# 7_Inch_Module.net
KiCad netlist of a schematic drawn in Altium Designer
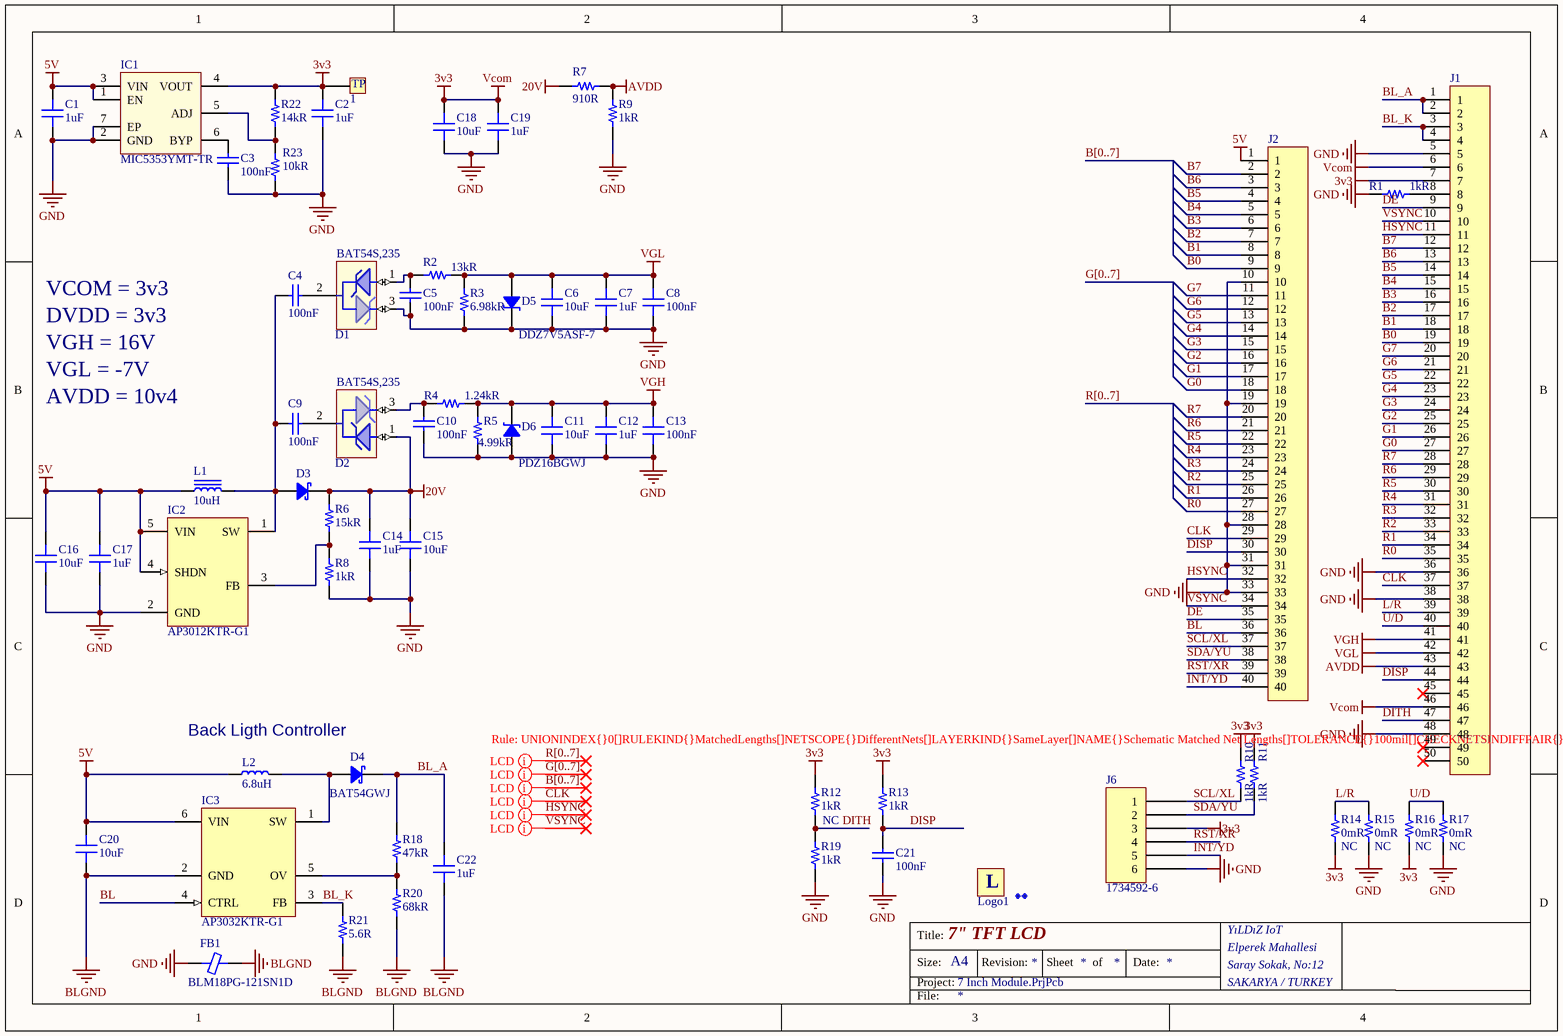
[diagram p0: 7 Inch Module.SchDoc]

(export (version "E")
  (design (tool "Eeschema 10.0.6"))
  (components
    (comp (ref "1")
      (value "Test Point")
      (footprint "TestPoint")
      (description "Custom Test Point")
      (libsource (lib "Muhammet_All_In_One") (part "Test Point"))
    )
    (comp (ref "C1")
      (value "1uF")
      (footprint "CAP 0603/1608")
      (description "Ceramic, SMT Capacitor")
      (fields
        (field (name "MANUFACTURER") "Samsung")
        (field (name "MANUFACTURER PART NUMBER") "CL10A105KP8NNNC")
      )
      (libsource (lib "yildizIoT Library") (part "Capacitor - Ceramic"))
    )
    (comp (ref "C2")
      (value "1uF")
      (footprint "CAP 0603/1608")
      (description "Ceramic, SMT Capacitor")
      (fields
        (field (name "MANUFACTURER") "Samsung")
        (field (name "MANUFACTURER PART NUMBER") "CL10A105KP8NNNC")
      )
      (libsource (lib "yildizIoT Library") (part "Capacitor - Ceramic"))
    )
    (comp (ref "C3")
      (value "100nF")
      (footprint "CAP 0603/1608")
      (description "Capacitor, Ceramic")
      (fields
        (field (name "MANUFACTURER") "Samsung")
        (field (name "MANUFACTURER PART NUMBER") "CL10A104KA8NNNC")
      )
      (libsource (lib "Muhammet_All_In_One") (part "Cap - Ceramic"))
    )
    (comp (ref "C4")
      (value "100nF")
      (footprint "CAP 0603/1608")
      (description "Capacitor, Ceramic")
      (fields
        (field (name "MANUFACTURER") "Samsung")
        (field (name "MANUFACTURER PART NUMBER") "CL10A104KA8NNNC")
      )
      (libsource (lib "Muhammet_All_In_One") (part "Cap - Ceramic"))
    )
    (comp (ref "C5")
      (value "100nF")
      (footprint "CAP 0603/1608")
      (description "Capacitor, Ceramic")
      (fields
        (field (name "MANUFACTURER") "Samsung")
        (field (name "MANUFACTURER PART NUMBER") "CL10A104KA8NNNC")
      )
      (libsource (lib "Muhammet_All_In_One") (part "Cap - Ceramic"))
    )
    (comp (ref "C6")
      (value "10uF")
      (footprint "CAP 0603/1608")
      (description "Ceramic, SMT Capacitor")
      (fields
        (field (name "MANUFACTURER") "Samsung")
        (field (name "MANUFACTURER PART NUMBER") "CL10A106MQ8NNNC")
      )
      (libsource (lib "yildizIoT Library") (part "Capacitor - Ceramic"))
    )
    (comp (ref "C7")
      (value "1uF")
      (footprint "CAP 0603/1608")
      (description "Ceramic, SMT Capacitor")
      (fields
        (field (name "MANUFACTURER") "Samsung")
        (field (name "MANUFACTURER PART NUMBER") "CL10A105KP8NNNC")
      )
      (libsource (lib "yildizIoT Library") (part "Capacitor - Ceramic"))
    )
    (comp (ref "C8")
      (value "100nF")
      (footprint "CAP 0603/1608")
      (description "Ceramic, SMT Capacitor")
      (fields
        (field (name "MANUFACTURER") "Samsung")
        (field (name "MANUFACTURER PART NUMBER") "CL10A104KA8NNNC")
      )
      (libsource (lib "yildizIoT Library") (part "Capacitor - Ceramic"))
    )
    (comp (ref "C9")
      (value "100nF")
      (footprint "CAP 0603/1608")
      (description "Capacitor, Ceramic")
      (fields
        (field (name "MANUFACTURER") "Samsung")
        (field (name "MANUFACTURER PART NUMBER") "CL10A104KA8NNNC")
      )
      (libsource (lib "Muhammet_All_In_One") (part "Cap - Ceramic"))
    )
    (comp (ref "C10")
      (value "100nF")
      (footprint "CAP 0603/1608")
      (description "Capacitor, Ceramic")
      (fields
        (field (name "MANUFACTURER") "Samsung")
        (field (name "MANUFACTURER PART NUMBER") "CL10A104KA8NNNC")
      )
      (libsource (lib "Muhammet_All_In_One") (part "Cap - Ceramic"))
    )
    (comp (ref "C11")
      (value "10uF")
      (footprint "CAP 0603/1608")
      (description "Ceramic, SMT Capacitor")
      (fields
        (field (name "MANUFACTURER") "Samsung")
        (field (name "MANUFACTURER PART NUMBER") "CL10A106MQ8NNNC")
      )
      (libsource (lib "yildizIoT Library") (part "Capacitor - Ceramic"))
    )
    (comp (ref "C12")
      (value "1uF")
      (footprint "CAP 0603/1608")
      (description "Ceramic, SMT Capacitor")
      (fields
        (field (name "MANUFACTURER") "Samsung")
        (field (name "MANUFACTURER PART NUMBER") "CL10A105KP8NNNC")
      )
      (libsource (lib "yildizIoT Library") (part "Capacitor - Ceramic"))
    )
    (comp (ref "C13")
      (value "100nF")
      (footprint "CAP 0603/1608")
      (description "Ceramic, SMT Capacitor")
      (fields
        (field (name "MANUFACTURER") "Samsung")
        (field (name "MANUFACTURER PART NUMBER") "CL10A104KA8NNNC")
      )
      (libsource (lib "yildizIoT Library") (part "Capacitor - Ceramic"))
    )
    (comp (ref "C14")
      (value "1uF")
      (footprint "CAP 0603/1608")
      (description "Ceramic, SMT Capacitor")
      (fields
        (field (name "MANUFACTURER") "Samsung")
        (field (name "MANUFACTURER PART NUMBER") "CL10A105KP8NNNC")
      )
      (libsource (lib "yildizIoT Library") (part "Capacitor - Ceramic"))
    )
    (comp (ref "C15")
      (value "10uF")
      (footprint "CAP 0603/1608")
      (description "Ceramic, SMT Capacitor")
      (fields
        (field (name "MANUFACTURER") "Samsung")
        (field (name "MANUFACTURER PART NUMBER") "CL10A106MQ8NNNC")
      )
      (libsource (lib "yildizIoT Library") (part "Capacitor - Ceramic"))
    )
    (comp (ref "C16")
      (value "10uF")
      (footprint "CAP 0603/1608")
      (description "Ceramic, SMT Capacitor")
      (fields
        (field (name "MANUFACTURER") "Samsung")
        (field (name "MANUFACTURER PART NUMBER") "CL10A106MQ8NNNC")
      )
      (libsource (lib "yildizIoT Library") (part "Capacitor - Ceramic"))
    )
    (comp (ref "C17")
      (value "1uF")
      (footprint "CAP 0603/1608")
      (description "Ceramic, SMT Capacitor")
      (fields
        (field (name "MANUFACTURER") "Samsung")
        (field (name "MANUFACTURER PART NUMBER") "CL10A105KP8NNNC")
      )
      (libsource (lib "yildizIoT Library") (part "Capacitor - Ceramic"))
    )
    (comp (ref "C18")
      (value "10uF")
      (footprint "CAP 0603/1608")
      (description "Ceramic, SMT Capacitor")
      (fields
        (field (name "MANUFACTURER") "Samsung")
        (field (name "MANUFACTURER PART NUMBER") "CL10A106MQ8NNNC")
      )
      (libsource (lib "yildizIoT Library") (part "Capacitor - Ceramic"))
    )
    (comp (ref "C19")
      (value "1uF")
      (footprint "CAP 0603/1608")
      (description "Ceramic, SMT Capacitor")
      (fields
        (field (name "MANUFACTURER") "Samsung")
        (field (name "MANUFACTURER PART NUMBER") "CL10A105KP8NNNC")
      )
      (libsource (lib "yildizIoT Library") (part "Capacitor - Ceramic"))
    )
    (comp (ref "C20")
      (value "10uF")
      (footprint "CAP 0603/1608")
      (description "Ceramic, SMT Capacitor")
      (fields
        (field (name "MANUFACTURER") "Samsung")
        (field (name "MANUFACTURER PART NUMBER") "CL10A106MQ8NNNC")
      )
      (libsource (lib "yildizIoT Library") (part "Capacitor - Ceramic"))
    )
    (comp (ref "C21")
      (value "100nF")
      (footprint "CAP 0603/1608")
      (description "Capacitor, Ceramic")
      (fields
        (field (name "MANUFACTURER") "Samsung")
        (field (name "MANUFACTURER PART NUMBER") "CL10A104KA8NNNC")
      )
      (libsource (lib "Muhammet_All_In_One") (part "Cap - Ceramic"))
    )
    (comp (ref "C22")
      (value "1uF")
      (footprint "CAP 0603/1608")
      (description "Ceramic, SMT Capacitor")
      (fields
        (field (name "MANUFACTURER") "Samsung")
        (field (name "MANUFACTURER PART NUMBER") "CL10A105KO8NNNC")
      )
      (libsource (lib "yildizIoT Library") (part "Capacitor - Ceramic"))
    )
    (comp (ref "D1")
      (value "BAT54S,235")
      (footprint "DIODES SOT-23-3")
      (description "TVS Array")
      (fields (field (name "MANUFACTURER") "Nexperia"))
      (libsource (lib "yildizIoT Library") (part "Diode Schottky Barier Array"))
    )
    (comp (ref "D2")
      (value "BAT54S,235")
      (footprint "DIODES SOT-23-3")
      (description "TVS Array")
      (fields (field (name "MANUFACTURER") "Nexperia"))
      (libsource (lib "") (part "Diode Schottky Barier Array_1"))
    )
    (comp (ref "D3")
      (value "1N5819HW-7-F")
      (footprint "SOD-123")
      (description "Zener Diode")
      (fields (field (name "MANUFACTURER") "Diodes"))
      (libsource (lib "yildizIoT Library") (part "Diode Schottky"))
    )
    (comp (ref "D4")
      (value "BAT54GWJ")
      (footprint "SOD-123")
      (description "Zener Diode")
      (fields (field (name "MANUFACTURER") "NXP Semiconductors"))
      (libsource (lib "yildizIoT Library") (part "Diode Schottky"))
    )
    (comp (ref "D5")
      (value "DDZ7V5ASF-7")
      (footprint "SOD323F")
      (description "Diodes Inc DDZ7V5ASF-7 Zener Diode, 7.0V 2.5% 500 mW SMT 2-Pin SOD-323F")
      (fields (field (name "MANUFACTURER") "Diodes"))
      (libsource (lib "yildizIoT Library") (part "Diode Zener"))
    )
    (comp (ref "D6")
      (value "PDZ16BGWJ")
      (footprint "SOD123F")
      (description "PDZ-B Series 16 V ±2% 400 mW Surface Mount Voltage Regulator Diode - SOD-323")
      (fields (field (name "MANUFACTURER") "Nexperia"))
      (libsource (lib "yildizIoT Library") (part "Diode Zener"))
    )
    (comp (ref "FB1")
      (value "BLM18PG-121SN1D")
      (footprint "FER 0603/1608")
      (description "SMT Ferrite Chip")
      (fields (field (name "MANUFACTURER") "Murata") (field (name "TOLERANCE") "25%"))
      (libsource (lib "yildizIoT Library") (part "Ferrite Chip"))
    )
    (comp (ref "Fid1")
      (value "Fiducial mark")
      (footprint "Fiducial")
      (description "Fiducial Mark")
      (fields (field (name "PART NUMBER") "Fid-Mark") (field (name "PUBLISHER") "Nordic Semiconductor"))
      (libsource (lib "yildizIoT Library") (part "Fiducial"))
    )
    (comp (ref "Fid2")
      (value "Fiducial mark")
      (footprint "Fiducial")
      (description "Fiducial Mark")
      (fields (field (name "PART NUMBER") "Fid-Mark") (field (name "PUBLISHER") "Nordic Semiconductor"))
      (libsource (lib "yildizIoT Library") (part "Fiducial"))
    )
    (comp (ref "IC1")
      (value "MIC5353YMT-TR")
      (footprint "MICREL MLF-6 1.6x1.6MM")
      (description "Integrated Circuit")
      (fields (field (name "MANUFACTURER") "Microchip"))
      (libsource (lib "yildizIoT Library") (part "MICROCHIP MIC5353"))
    )
    (comp (ref "IC2")
      (value "AP3012KTR-G1")
      (footprint "DIODES SOT-23-5 W5")
      (description "1.5MHz STEP-UP DC-DC CONVERTER")
      (fields (field (name "MANUFACTURER") "Diodes"))
      (libsource (lib "yildizIoT Library") (part "DIODES AP3012"))
    )
    (comp (ref "IC3")
      (value "AP3032KTR-G1")
      (footprint "DIODES SOT-23-6 W6")
      (fields (field (name "MANUFACTURER") "Diodes"))
      (libsource (lib "yildizIoT Library") (part "DIODES AP3032"))
    )
    (comp (ref "J1")
      (value "62684-501100ALF")
      (footprint "Amphenol 62684-501100ALF")
      (description "Connector")
      (fields (field (name "MANUFACTURER") "Amphenol FCI"))
      (libsource (lib "yildizIoT Library") (part "FPC-50"))
    )
    (comp (ref "J2")
      (value "62684-401100ALF")
      (footprint "Amphenol 62684-401100ALF")
      (description "Connector")
      (fields (field (name "MANUFACTURER") "Amphenol FCI"))
      (libsource (lib "yildizIoT Library") (part "FPC-40"))
    )
    (comp (ref "J6")
      (value "1734592-6")
      (footprint "FPC-6")
      (fields (field (name "MANUFACTURER") "TE Connectivity"))
      (libsource (lib "yildizIoT Library") (part "6 Pin"))
    )
    (comp (ref "L1")
      (value "10uH")
      (footprint "TAIYO YUDEN MAMK2520T1R0M")
      (fields
        (field (name "MANUFACTURER") "Delta Electronics/Cyntec")
        (field (name "MANUFACTURER PART NUMBER") "SDET25201T-100MS")
        (field (name "TOLERANCE") "20%")
      )
      (libsource (lib "yildizIoT Library") (part "Inductor Iron Core"))
    )
    (comp (ref "L2")
      (value "6.8uH")
      (footprint "FER 0805/2012")
      (fields
        (field (name "MANUFACTURER") "TDK")
        (field (name "MANUFACTURER PART NUMBER") "MLZ2012M6R8WT000")
        (field (name "TOLERANCE") "20%")
      )
      (libsource (lib "yildizIoT Library") (part "Inductor Air Core"))
    )
    (comp (ref "Logo1")
      (value "Logo symbol")
      (footprint "LOGO_YILDIZIOT")
      (description "Schematic symbol for Logo")
      (libsource (lib "yildizIoT Library") (part "Logo"))
    )
    (comp (ref "R1")
      (value "1kR")
      (footprint "RES 0603/1608")
      (description "Ceramic, SMT Capacitor")
      (fields
        (field (name "MANUFACTURER") "Yageo")
        (field (name "MANUFACTURER PART NUMBER") "RC0603FR-071KL")
      )
      (libsource (lib "yildizIoT Library") (part "Resistor_Chip"))
    )
    (comp (ref "R2")
      (value "13kR")
      (footprint "RES 0603/1608")
      (description "Ceramic, SMT Capacitor")
      (fields
        (field (name "MANUFACTURER") "Yageo")
        (field (name "MANUFACTURER PART NUMBER") "RC0603JR-0713KL")
      )
      (libsource (lib "yildizIoT Library") (part "Resistor_Chip"))
    )
    (comp (ref "R3")
      (value "6.98kR")
      (footprint "RES 0603/1608")
      (description "Ceramic, SMT Capacitor")
      (fields
        (field (name "MANUFACTURER") "Yageo")
        (field (name "MANUFACTURER PART NUMBER") "RC0603FR-076K98L")
      )
      (libsource (lib "yildizIoT Library") (part "Resistor_Chip"))
    )
    (comp (ref "R4")
      (value "1.24kR")
      (footprint "RES 0603/1608")
      (description "Ceramic, SMT Capacitor")
      (fields
        (field (name "MANUFACTURER") "Yageo")
        (field (name "MANUFACTURER PART NUMBER") "RC0603FR-071K24L")
      )
      (libsource (lib "yildizIoT Library") (part "Resistor_Chip"))
    )
    (comp (ref "R5")
      (value "4.99kR")
      (footprint "RES 0603/1608")
      (description "Ceramic, SMT Capacitor")
      (fields
        (field (name "MANUFACTURER") "Yageo Phycomp")
        (field (name "MANUFACTURER PART NUMBER") "RC0603FR-074K99L")
      )
      (libsource (lib "yildizIoT Library") (part "Resistor_Chip"))
    )
    (comp (ref "R6")
      (value "15kR")
      (footprint "RES 0603/1608")
      (description "Ceramic, SMT Capacitor")
      (fields
        (field (name "MANUFACTURER") "Yageo")
        (field (name "MANUFACTURER PART NUMBER") "RC0603FR-0715KL")
      )
      (libsource (lib "yildizIoT Library") (part "Resistor_Chip"))
    )
    (comp (ref "R7")
      (value "910R")
      (footprint "RES 0603/1608")
      (description "Ceramic, SMT Capacitor")
      (fields
        (field (name "MANUFACTURER") "Yageo")
        (field (name "MANUFACTURER PART NUMBER") "RC0603FR-07910RL")
      )
      (libsource (lib "yildizIoT Library") (part "Resistor_Chip"))
    )
    (comp (ref "R8")
      (value "1kR")
      (footprint "RES 0603/1608")
      (description "Ceramic, SMT Capacitor")
      (fields
        (field (name "MANUFACTURER") "Yageo")
        (field (name "MANUFACTURER PART NUMBER") "RC0603FR-071KL")
      )
      (libsource (lib "yildizIoT Library") (part "Resistor_Chip"))
    )
    (comp (ref "R9")
      (value "1kR")
      (footprint "RES 0603/1608")
      (description "Ceramic, SMT Capacitor")
      (fields
        (field (name "MANUFACTURER") "Yageo")
        (field (name "MANUFACTURER PART NUMBER") "RC0603FR-071KL")
      )
      (libsource (lib "yildizIoT Library") (part "Resistor_Chip"))
    )
    (comp (ref "R10")
      (value "1kR")
      (footprint "RES 0603/1608")
      (description "Ceramic, SMT Capacitor")
      (fields
        (field (name "MANUFACTURER") "Yageo")
        (field (name "MANUFACTURER PART NUMBER") "RC0603FR-071KL")
      )
      (libsource (lib "yildizIoT Library") (part "Resistor_Chip"))
    )
    (comp (ref "R11")
      (value "1kR")
      (footprint "RES 0603/1608")
      (description "Ceramic, SMT Capacitor")
      (fields
        (field (name "MANUFACTURER") "Yageo")
        (field (name "MANUFACTURER PART NUMBER") "RC0603FR-071KL")
      )
      (libsource (lib "yildizIoT Library") (part "Resistor_Chip"))
    )
    (comp (ref "R12")
      (value "1kR")
      (footprint "RES 0603/1608")
      (description "Ceramic, SMT Capacitor")
      (fields
        (field (name "NC") "NC")
        (field (name "MANUFACTURER") "Yageo")
        (field (name "MANUFACTURER PART NUMBER") "RC0603FR-071KL")
      )
      (libsource (lib "yildizIoT Library") (part "Resistor_Chip"))
    )
    (comp (ref "R13")
      (value "1kR")
      (footprint "RES 0603/1608")
      (description "Ceramic, SMT Capacitor")
      (fields
        (field (name "MANUFACTURER") "Yageo")
        (field (name "MANUFACTURER PART NUMBER") "RC0603FR-071KL")
      )
      (libsource (lib "yildizIoT Library") (part "Resistor_Chip"))
    )
    (comp (ref "R14")
      (value "0mR")
      (footprint "RES 0603/1608")
      (description "Ceramic, SMT Capacitor")
      (fields
        (field (name "MANUFACTURER") "Stackpole Electronics")
        (field (name "MANUFACTURER PART NUMBER") "RMCF0603ZT0R00")
        (field (name "NC") "NC")
      )
      (libsource (lib "yildizIoT Library") (part "Resistor_Chip"))
    )
    (comp (ref "R15")
      (value "0mR")
      (footprint "RES 0603/1608")
      (description "Ceramic, SMT Capacitor")
      (fields
        (field (name "MANUFACTURER") "Stackpole Electronics")
        (field (name "MANUFACTURER PART NUMBER") "RMCF0603ZT0R00")
        (field (name "NC") "NC")
      )
      (libsource (lib "yildizIoT Library") (part "Resistor_Chip"))
    )
    (comp (ref "R16")
      (value "0mR")
      (footprint "RES 0603/1608")
      (description "Ceramic, SMT Capacitor")
      (fields
        (field (name "MANUFACTURER") "Stackpole Electronics")
        (field (name "MANUFACTURER PART NUMBER") "RMCF0603ZT0R00")
        (field (name "NC") "NC")
      )
      (libsource (lib "yildizIoT Library") (part "Resistor_Chip"))
    )
    (comp (ref "R17")
      (value "0mR")
      (footprint "RES 0603/1608")
      (description "Ceramic, SMT Capacitor")
      (fields
        (field (name "MANUFACTURER") "Stackpole Electronics")
        (field (name "MANUFACTURER PART NUMBER") "RMCF0603ZT0R00")
        (field (name "NC") "NC")
      )
      (libsource (lib "yildizIoT Library") (part "Resistor_Chip"))
    )
    (comp (ref "R18")
      (value "47kR")
      (footprint "RES 0603/1608")
      (description "Ceramic, SMT Capacitor")
      (fields
        (field (name "MANUFACTURER") "Yageo")
        (field (name "MANUFACTURER PART NUMBER") "RC0603FR-0747KL")
      )
      (libsource (lib "yildizIoT Library") (part "Resistor_Chip"))
    )
    (comp (ref "R19")
      (value "1kR")
      (footprint "RES 0603/1608")
      (description "Ceramic, SMT Capacitor")
      (fields
        (field (name "MANUFACTURER") "Yageo")
        (field (name "MANUFACTURER PART NUMBER") "RC0603FR-071KL")
      )
      (libsource (lib "yildizIoT Library") (part "Resistor_Chip"))
    )
    (comp (ref "R20")
      (value "68kR")
      (footprint "RES 0603/1608")
      (description "Ceramic, SMT Capacitor")
      (fields
        (field (name "MANUFACTURER") "Yageo")
        (field (name "MANUFACTURER PART NUMBER") "RC0603FR-0768KL")
      )
      (libsource (lib "yildizIoT Library") (part "Resistor_Chip"))
    )
    (comp (ref "R21")
      (value "5.6R")
      (footprint "RES 1206/3216")
      (description "Ceramic, SMT Capacitor")
      (fields (field (name "MANUFACTURER") "Rohm") (field (name "MANUFACTURER PART NUMBER") "ESR18EZPJ5R6"))
      (libsource (lib "yildizIoT Library") (part "Resistor_Chip"))
    )
    (comp (ref "R22")
      (value "14kR")
      (footprint "RES 0603/1608")
      (description "Ceramic, SMT Capacitor")
      (fields
        (field (name "MANUFACTURER") "Yageo")
        (field (name "MANUFACTURER PART NUMBER") "RC0603FR-0714KL")
      )
      (libsource (lib "yildizIoT Library") (part "Resistor_Chip"))
    )
    (comp (ref "R23")
      (value "10kR")
      (footprint "RES 0603/1608")
      (description "Ceramic, SMT Capacitor")
      (fields
        (field (name "MANUFACTURER") "Stackpole Electronics")
        (field (name "MANUFACTURER PART NUMBER") "RNCP0603FTD10K0")
      )
      (libsource (lib "yildizIoT Library") (part "Resistor_Chip"))
    )
  )
  (nets
    (net (code "1") (name "/B0") (class "Default")
      (node (ref "J1") (pin "19") (pinfunction "19_19") (pintype "passive"))
      (node (ref "J2") (pin "9") (pinfunction "9_9") (pintype "passive"))
    )
    (net (code "2") (name "/B1") (class "Default")
      (node (ref "J1") (pin "18") (pinfunction "18_18") (pintype "passive"))
      (node (ref "J2") (pin "8") (pinfunction "8_8") (pintype "passive"))
    )
    (net (code "3") (name "/B2") (class "Default")
      (node (ref "J1") (pin "17") (pinfunction "17_17") (pintype "passive"))
      (node (ref "J2") (pin "7") (pinfunction "7_7") (pintype "passive"))
    )
    (net (code "4") (name "/B3") (class "Default")
      (node (ref "J1") (pin "16") (pinfunction "16_16") (pintype "passive"))
      (node (ref "J2") (pin "6") (pinfunction "6_6") (pintype "passive"))
    )
    (net (code "5") (name "/B4") (class "Default")
      (node (ref "J1") (pin "15") (pinfunction "15_15") (pintype "passive"))
      (node (ref "J2") (pin "5") (pinfunction "5_5") (pintype "passive"))
    )
    (net (code "6") (name "/B5") (class "Default")
      (node (ref "J1") (pin "14") (pinfunction "14_14") (pintype "passive"))
      (node (ref "J2") (pin "4") (pinfunction "4_4") (pintype "passive"))
    )
    (net (code "7") (name "/B6") (class "Default")
      (node (ref "J1") (pin "13") (pinfunction "13_13") (pintype "passive"))
      (node (ref "J2") (pin "3") (pinfunction "3_3") (pintype "passive"))
    )
    (net (code "8") (name "/B7") (class "Default")
      (node (ref "J1") (pin "12") (pinfunction "12_12") (pintype "passive"))
      (node (ref "J2") (pin "2") (pinfunction "2_2") (pintype "passive"))
    )
    (net (code "9") (name "/BL") (class "Default")
      (node (ref "IC3") (pin "4") (pinfunction "CTRL_4") (pintype "input"))
      (node (ref "J2") (pin "36") (pinfunction "36_36") (pintype "passive"))
    )
    (net (code "10") (name "/BL_A") (class "Default")
      (node (ref "C22") (pin "2") (pinfunction "2_2") (pintype "passive"))
      (node (ref "D4") (pin "2") (pinfunction "2_2") (pintype "passive"))
      (node (ref "J1") (pin "1") (pinfunction "1_1") (pintype "passive"))
      (node (ref "J1") (pin "2") (pinfunction "2_2") (pintype "passive"))
      (node (ref "R18") (pin "2") (pinfunction "2_2") (pintype "passive"))
    )
    (net (code "11") (name "/BL_K") (class "Default")
      (node (ref "IC3") (pin "3") (pinfunction "FB_3") (pintype "power_in"))
      (node (ref "J1") (pin "3") (pinfunction "3_3") (pintype "passive"))
      (node (ref "J1") (pin "4") (pinfunction "4_4") (pintype "passive"))
      (node (ref "R21") (pin "2") (pinfunction "2_2") (pintype "passive"))
    )
    (net (code "13") (name "/CLK") (class "Default")
      (node (ref "J1") (pin "37") (pinfunction "37_37") (pintype "passive"))
      (node (ref "J2") (pin "29") (pinfunction "29_29") (pintype "passive"))
    )
    (net (code "14") (name "/DE") (class "Default")
      (node (ref "J1") (pin "9") (pinfunction "9_9") (pintype "passive"))
      (node (ref "J2") (pin "35") (pinfunction "35_35") (pintype "passive"))
    )
    (net (code "15") (name "/DISP") (class "Default")
      (node (ref "C21") (pin "2") (pinfunction "2_2") (pintype "passive"))
      (node (ref "J1") (pin "44") (pinfunction "44_44") (pintype "passive"))
      (node (ref "J2") (pin "30") (pinfunction "30_30") (pintype "passive"))
      (node (ref "R13") (pin "1") (pinfunction "1_1") (pintype "passive"))
    )
    (net (code "16") (name "/DITH") (class "Default")
      (node (ref "J1") (pin "47") (pinfunction "47_47") (pintype "passive"))
      (node (ref "R12") (pin "2") (pinfunction "2_2") (pintype "passive"))
      (node (ref "R19") (pin "1") (pinfunction "1_1") (pintype "passive"))
    )
    (net (code "17") (name "/G0") (class "Default")
      (node (ref "J1") (pin "27") (pinfunction "27_27") (pintype "passive"))
      (node (ref "J2") (pin "18") (pinfunction "18_18") (pintype "passive"))
    )
    (net (code "18") (name "/G1") (class "Default")
      (node (ref "J1") (pin "26") (pinfunction "26_26") (pintype "passive"))
      (node (ref "J2") (pin "17") (pinfunction "17_17") (pintype "passive"))
    )
    (net (code "19") (name "/G2") (class "Default")
      (node (ref "J1") (pin "25") (pinfunction "25_25") (pintype "passive"))
      (node (ref "J2") (pin "16") (pinfunction "16_16") (pintype "passive"))
    )
    (net (code "20") (name "/G3") (class "Default")
      (node (ref "J1") (pin "24") (pinfunction "24_24") (pintype "passive"))
      (node (ref "J2") (pin "15") (pinfunction "15_15") (pintype "passive"))
    )
    (net (code "21") (name "/G4") (class "Default")
      (node (ref "J1") (pin "23") (pinfunction "23_23") (pintype "passive"))
      (node (ref "J2") (pin "14") (pinfunction "14_14") (pintype "passive"))
    )
    (net (code "22") (name "/G5") (class "Default")
      (node (ref "J1") (pin "22") (pinfunction "22_22") (pintype "passive"))
      (node (ref "J2") (pin "13") (pinfunction "13_13") (pintype "passive"))
    )
    (net (code "23") (name "/G6") (class "Default")
      (node (ref "J1") (pin "21") (pinfunction "21_21") (pintype "passive"))
      (node (ref "J2") (pin "12") (pinfunction "12_12") (pintype "passive"))
    )
    (net (code "24") (name "/G7") (class "Default")
      (node (ref "J1") (pin "20") (pinfunction "20_20") (pintype "passive"))
      (node (ref "J2") (pin "11") (pinfunction "11_11") (pintype "passive"))
    )
    (net (code "26") (name "/HSYNC") (class "Default")
      (node (ref "J1") (pin "11") (pinfunction "11_11") (pintype "passive"))
      (node (ref "J2") (pin "32") (pinfunction "32_32") (pintype "passive"))
    )
    (net (code "27") (name "/INT{slash}YD") (class "Default")
      (node (ref "J2") (pin "40") (pinfunction "40_40") (pintype "passive"))
      (node (ref "J6") (pin "5") (pinfunction "5_5") (pintype "passive"))
    )
    (net (code "28") (name "/L{slash}R") (class "Default")
      (node (ref "J1") (pin "39") (pinfunction "39_39") (pintype "passive"))
      (node (ref "R14") (pin "2") (pinfunction "2_2") (pintype "passive"))
      (node (ref "R15") (pin "2") (pinfunction "2_2") (pintype "passive"))
    )
    (net (code "29") (name "/R0") (class "Default")
      (node (ref "J1") (pin "35") (pinfunction "35_35") (pintype "passive"))
      (node (ref "J2") (pin "27") (pinfunction "27_27") (pintype "passive"))
    )
    (net (code "30") (name "/R1") (class "Default")
      (node (ref "J1") (pin "34") (pinfunction "34_34") (pintype "passive"))
      (node (ref "J2") (pin "26") (pinfunction "26_26") (pintype "passive"))
    )
    (net (code "31") (name "/R2") (class "Default")
      (node (ref "J1") (pin "33") (pinfunction "33_33") (pintype "passive"))
      (node (ref "J2") (pin "25") (pinfunction "25_25") (pintype "passive"))
    )
    (net (code "32") (name "/R3") (class "Default")
      (node (ref "J1") (pin "32") (pinfunction "32_32") (pintype "passive"))
      (node (ref "J2") (pin "24") (pinfunction "24_24") (pintype "passive"))
    )
    (net (code "33") (name "/R4") (class "Default")
      (node (ref "J1") (pin "31") (pinfunction "31_31") (pintype "passive"))
      (node (ref "J2") (pin "23") (pinfunction "23_23") (pintype "passive"))
    )
    (net (code "34") (name "/R5") (class "Default")
      (node (ref "J1") (pin "30") (pinfunction "30_30") (pintype "passive"))
      (node (ref "J2") (pin "22") (pinfunction "22_22") (pintype "passive"))
    )
    (net (code "35") (name "/R6") (class "Default")
      (node (ref "J1") (pin "29") (pinfunction "29_29") (pintype "passive"))
      (node (ref "J2") (pin "21") (pinfunction "21_21") (pintype "passive"))
    )
    (net (code "36") (name "/R7") (class "Default")
      (node (ref "J1") (pin "28") (pinfunction "28_28") (pintype "passive"))
      (node (ref "J2") (pin "20") (pinfunction "20_20") (pintype "passive"))
    )
    (net (code "37") (name "/RST{slash}XR") (class "Default")
      (node (ref "J2") (pin "39") (pinfunction "39_39") (pintype "passive"))
      (node (ref "J6") (pin "4") (pinfunction "4_4") (pintype "passive"))
    )
    (net (code "39") (name "/SCL{slash}XL") (class "Default")
      (node (ref "J2") (pin "37") (pinfunction "37_37") (pintype "passive"))
      (node (ref "J6") (pin "1") (pinfunction "1_1") (pintype "passive"))
      (node (ref "R10") (pin "2") (pinfunction "2_2") (pintype "passive"))
    )
    (net (code "40") (name "/SDA{slash}YU") (class "Default")
      (node (ref "J2") (pin "38") (pinfunction "38_38") (pintype "passive"))
      (node (ref "J6") (pin "2") (pinfunction "2_2") (pintype "passive"))
      (node (ref "R11") (pin "2") (pinfunction "2_2") (pintype "passive"))
    )
    (net (code "41") (name "/U{slash}D") (class "Default")
      (node (ref "J1") (pin "40") (pinfunction "40_40") (pintype "passive"))
      (node (ref "R16") (pin "2") (pinfunction "2_2") (pintype "passive"))
      (node (ref "R17") (pin "2") (pinfunction "2_2") (pintype "passive"))
    )
    (net (code "42") (name "/VSYNC") (class "Default")
      (node (ref "J1") (pin "10") (pinfunction "10_10") (pintype "passive"))
      (node (ref "J2") (pin "34") (pinfunction "34_34") (pintype "passive"))
    )
    (net (code "43") (name "3v3") (class "Default")
      (node (ref "1") (pin "1") (pinfunction "1_1") (pintype "passive"))
      (node (ref "C18") (pin "2") (pinfunction "2_2") (pintype "passive"))
      (node (ref "C19") (pin "2") (pinfunction "2_2") (pintype "passive"))
      (node (ref "C2") (pin "2") (pinfunction "2_2") (pintype "passive"))
      (node (ref "IC1") (pin "4") (pinfunction "VOUT_4") (pintype "passive"))
      (node (ref "J1") (pin "46") (pinfunction "46_46") (pintype "passive"))
      (node (ref "J1") (pin "6") (pinfunction "6_6") (pintype "passive"))
      (node (ref "J1") (pin "7") (pinfunction "7_7") (pintype "passive"))
      (node (ref "J6") (pin "3") (pinfunction "3_3") (pintype "passive"))
      (node (ref "R10") (pin "1") (pinfunction "1_1") (pintype "passive"))
      (node (ref "R11") (pin "1") (pinfunction "1_1") (pintype "passive"))
      (node (ref "R12") (pin "1") (pinfunction "1_1") (pintype "passive"))
      (node (ref "R13") (pin "2") (pinfunction "2_2") (pintype "passive"))
      (node (ref "R14") (pin "1") (pinfunction "1_1") (pintype "passive"))
      (node (ref "R16") (pin "1") (pinfunction "1_1") (pintype "passive"))
      (node (ref "R22") (pin "2") (pinfunction "2_2") (pintype "passive"))
    )
    (net (code "44") (name "5V") (class "Default")
      (node (ref "C1") (pin "2") (pinfunction "2_2") (pintype "passive"))
      (node (ref "C16") (pin "2") (pinfunction "2_2") (pintype "passive"))
      (node (ref "C17") (pin "2") (pinfunction "2_2") (pintype "passive"))
      (node (ref "C20") (pin "2") (pinfunction "2_2") (pintype "passive"))
      (node (ref "IC1") (pin "1") (pinfunction "EN_1") (pintype "passive"))
      (node (ref "IC1") (pin "3") (pinfunction "VIN_3") (pintype "passive"))
      (node (ref "IC2") (pin "4") (pinfunction "SHDN_4") (pintype "input"))
      (node (ref "IC2") (pin "5") (pinfunction "VIN_5") (pintype "power_in"))
      (node (ref "IC3") (pin "6") (pinfunction "VIN_6") (pintype "power_in"))
      (node (ref "J2") (pin "1") (pinfunction "1_1") (pintype "passive"))
      (node (ref "L1") (pin "1") (pinfunction "1_1") (pintype "passive"))
      (node (ref "L2") (pin "1") (pinfunction "1_1") (pintype "passive"))
    )
    (net (code "45") (name "20V") (class "Default")
      (node (ref "C14") (pin "2") (pinfunction "2_2") (pintype "passive"))
      (node (ref "C15") (pin "2") (pinfunction "2_2") (pintype "passive"))
      (node (ref "D2") (pin "1") (pinfunction "1_1") (pintype "bidirectional"))
      (node (ref "D3") (pin "2") (pinfunction "2_2") (pintype "passive"))
      (node (ref "R6") (pin "2") (pinfunction "2_2") (pintype "passive"))
      (node (ref "R7") (pin "1") (pinfunction "1_1") (pintype "passive"))
    )
    (net (code "46") (name "AVDD") (class "Default")
      (node (ref "J1") (pin "43") (pinfunction "43_43") (pintype "passive"))
      (node (ref "R7") (pin "2") (pinfunction "2_2") (pintype "passive"))
      (node (ref "R9") (pin "1") (pinfunction "1_1") (pintype "passive"))
    )
    (net (code "47") (name "BLGND") (class "Default")
      (node (ref "C20") (pin "1") (pinfunction "1_1") (pintype "passive"))
      (node (ref "C22") (pin "1") (pinfunction "1_1") (pintype "passive"))
      (node (ref "FB1") (pin "2") (pinfunction "2_2") (pintype "passive"))
      (node (ref "IC3") (pin "2") (pinfunction "GND_2") (pintype "power_in"))
      (node (ref "R20") (pin "1") (pinfunction "1_1") (pintype "passive"))
      (node (ref "R21") (pin "1") (pinfunction "1_1") (pintype "passive"))
    )
    (net (code "48") (name "GND") (class "Default")
      (node (ref "C1") (pin "1") (pinfunction "1_1") (pintype "passive"))
      (node (ref "C10") (pin "1") (pinfunction "1_1") (pintype "passive"))
      (node (ref "C11") (pin "1") (pinfunction "1_1") (pintype "passive"))
      (node (ref "C12") (pin "1") (pinfunction "1_1") (pintype "passive"))
      (node (ref "C13") (pin "1") (pinfunction "1_1") (pintype "passive"))
      (node (ref "C14") (pin "1") (pinfunction "1_1") (pintype "passive"))
      (node (ref "C15") (pin "1") (pinfunction "1_1") (pintype "passive"))
      (node (ref "C16") (pin "1") (pinfunction "1_1") (pintype "passive"))
      (node (ref "C17") (pin "1") (pinfunction "1_1") (pintype "passive"))
      (node (ref "C18") (pin "1") (pinfunction "1_1") (pintype "passive"))
      (node (ref "C19") (pin "1") (pinfunction "1_1") (pintype "passive"))
      (node (ref "C2") (pin "1") (pinfunction "1_1") (pintype "passive"))
      (node (ref "C21") (pin "1") (pinfunction "1_1") (pintype "passive"))
      (node (ref "C3") (pin "1") (pinfunction "1_1") (pintype "passive"))
      (node (ref "C5") (pin "1") (pinfunction "1_1") (pintype "passive"))
      (node (ref "C6") (pin "1") (pinfunction "1_1") (pintype "passive"))
      (node (ref "C7") (pin "1") (pinfunction "1_1") (pintype "passive"))
      (node (ref "C8") (pin "1") (pinfunction "1_1") (pintype "passive"))
      (node (ref "D1") (pin "3") (pinfunction "3_3") (pintype "bidirectional"))
      (node (ref "D5") (pin "2") (pinfunction "2_2") (pintype "passive"))
      (node (ref "D6") (pin "1") (pinfunction "1_1") (pintype "passive"))
      (node (ref "FB1") (pin "1") (pinfunction "1_1") (pintype "passive"))
      (node (ref "IC1") (pin "2") (pinfunction "GND_2") (pintype "passive"))
      (node (ref "IC1") (pin "7") (pinfunction "EP_7") (pintype "power_in"))
      (node (ref "IC2") (pin "2") (pinfunction "GND_2") (pintype "power_in"))
      (node (ref "J1") (pin "36") (pinfunction "36_36") (pintype "passive"))
      (node (ref "J1") (pin "38") (pinfunction "38_38") (pintype "passive"))
      (node (ref "J1") (pin "48") (pinfunction "48_48") (pintype "passive"))
      (node (ref "J1") (pin "5") (pinfunction "5_5") (pintype "passive"))
      (node (ref "J2") (pin "10") (pinfunction "10_10") (pintype "passive"))
      (node (ref "J2") (pin "19") (pinfunction "19_19") (pintype "passive"))
      (node (ref "J2") (pin "28") (pinfunction "28_28") (pintype "passive"))
      (node (ref "J2") (pin "31") (pinfunction "31_31") (pintype "passive"))
      (node (ref "J2") (pin "33") (pinfunction "33_33") (pintype "passive"))
      (node (ref "J6") (pin "6") (pinfunction "6_6") (pintype "passive"))
      (node (ref "R1") (pin "1") (pinfunction "1_1") (pintype "passive"))
      (node (ref "R15") (pin "1") (pinfunction "1_1") (pintype "passive"))
      (node (ref "R17") (pin "1") (pinfunction "1_1") (pintype "passive"))
      (node (ref "R19") (pin "2") (pinfunction "2_2") (pintype "passive"))
      (node (ref "R23") (pin "2") (pinfunction "2_2") (pintype "passive"))
      (node (ref "R3") (pin "1") (pinfunction "1_1") (pintype "passive"))
      (node (ref "R5") (pin "1") (pinfunction "1_1") (pintype "passive"))
      (node (ref "R8") (pin "2") (pinfunction "2_2") (pintype "passive"))
      (node (ref "R9") (pin "2") (pinfunction "2_2") (pintype "passive"))
    )
    (net (code "49") (name "Net-(C4-Pad1)") (class "Default")
      (node (ref "C4") (pin "1") (pinfunction "1_1") (pintype "passive"))
      (node (ref "D1") (pin "2") (pinfunction "2_2") (pintype "power_in"))
    )
    (net (code "50") (name "Net-(C5-Pad2)") (class "Default")
      (node (ref "C5") (pin "2") (pinfunction "2_2") (pintype "passive"))
      (node (ref "D1") (pin "1") (pinfunction "1_1") (pintype "bidirectional"))
      (node (ref "R2") (pin "1") (pinfunction "1_1") (pintype "passive"))
    )
    (net (code "51") (name "Net-(C9-Pad1)") (class "Default")
      (node (ref "C9") (pin "1") (pinfunction "1_1") (pintype "passive"))
      (node (ref "D2") (pin "2") (pinfunction "2_2") (pintype "power_in"))
    )
    (net (code "52") (name "Net-(C10-Pad2)") (class "Default")
      (node (ref "C10") (pin "2") (pinfunction "2_2") (pintype "passive"))
      (node (ref "D2") (pin "3") (pinfunction "3_3") (pintype "bidirectional"))
      (node (ref "R4") (pin "1") (pinfunction "1_1") (pintype "passive"))
    )
    (net (code "53") (name "Net-(IC1-ADJ)") (class "Default")
      (node (ref "IC1") (pin "5") (pinfunction "ADJ_5") (pintype "passive"))
      (node (ref "R22") (pin "1") (pinfunction "1_1") (pintype "passive"))
      (node (ref "R23") (pin "1") (pinfunction "1_1") (pintype "passive"))
    )
    (net (code "54") (name "Net-(IC1-BYP)") (class "Default")
      (node (ref "C3") (pin "2") (pinfunction "2_2") (pintype "passive"))
      (node (ref "IC1") (pin "6") (pinfunction "BYP_6") (pintype "passive"))
    )
    (net (code "55") (name "Net-(IC2-FB)") (class "Default")
      (node (ref "IC2") (pin "3") (pinfunction "FB_3") (pintype "power_in"))
      (node (ref "R6") (pin "1") (pinfunction "1_1") (pintype "passive"))
      (node (ref "R8") (pin "1") (pinfunction "1_1") (pintype "passive"))
    )
    (net (code "56") (name "Net-(IC2-SW)") (class "Default")
      (node (ref "C4") (pin "2") (pinfunction "2_2") (pintype "passive"))
      (node (ref "C9") (pin "2") (pinfunction "2_2") (pintype "passive"))
      (node (ref "D3") (pin "1") (pinfunction "1_1") (pintype "passive"))
      (node (ref "IC2") (pin "1") (pinfunction "SW_1") (pintype "power_in"))
      (node (ref "L1") (pin "2") (pinfunction "2_2") (pintype "passive"))
    )
    (net (code "57") (name "Net-(IC3-OV)") (class "Default")
      (node (ref "IC3") (pin "5") (pinfunction "OV_5") (pintype "power_in"))
      (node (ref "R18") (pin "1") (pinfunction "1_1") (pintype "passive"))
      (node (ref "R20") (pin "2") (pinfunction "2_2") (pintype "passive"))
    )
    (net (code "58") (name "Net-(IC3-SW)") (class "Default")
      (node (ref "D4") (pin "1") (pinfunction "1_1") (pintype "passive"))
      (node (ref "IC3") (pin "1") (pinfunction "SW_1") (pintype "power_in"))
      (node (ref "L2") (pin "2") (pinfunction "2_2") (pintype "passive"))
    )
    (net (code "59") (name "Net-(J1-Pad8)") (class "Default")
      (node (ref "J1") (pin "8") (pinfunction "8_8") (pintype "passive"))
      (node (ref "R1") (pin "2") (pinfunction "2_2") (pintype "passive"))
    )
    (net (code "60") (name "VGH") (class "Default")
      (node (ref "C11") (pin "2") (pinfunction "2_2") (pintype "passive"))
      (node (ref "C12") (pin "2") (pinfunction "2_2") (pintype "passive"))
      (node (ref "C13") (pin "2") (pinfunction "2_2") (pintype "passive"))
      (node (ref "D6") (pin "2") (pinfunction "2_2") (pintype "passive"))
      (node (ref "J1") (pin "41") (pinfunction "41_41") (pintype "passive"))
      (node (ref "R4") (pin "2") (pinfunction "2_2") (pintype "passive"))
      (node (ref "R5") (pin "2") (pinfunction "2_2") (pintype "passive"))
    )
    (net (code "61") (name "VGL") (class "Default")
      (node (ref "C6") (pin "2") (pinfunction "2_2") (pintype "passive"))
      (node (ref "C7") (pin "2") (pinfunction "2_2") (pintype "passive"))
      (node (ref "C8") (pin "2") (pinfunction "2_2") (pintype "passive"))
      (node (ref "D5") (pin "1") (pinfunction "1_1") (pintype "passive"))
      (node (ref "J1") (pin "42") (pinfunction "42_42") (pintype "passive"))
      (node (ref "R2") (pin "2") (pinfunction "2_2") (pintype "passive"))
      (node (ref "R3") (pin "2") (pinfunction "2_2") (pintype "passive"))
    )
    (net (code "62") (name "unconnected-(J1-Pad45)") (class "Default")
      (node (ref "J1") (pin "45") (pinfunction "45_45") (pintype "passive+no_connect"))
    )
    (net (code "63") (name "unconnected-(J1-Pad49)") (class "Default")
      (node (ref "J1") (pin "49") (pinfunction "49_49") (pintype "passive+no_connect"))
    )
    (net (code "64") (name "unconnected-(J1-Pad50)") (class "Default")
      (node (ref "J1") (pin "50") (pinfunction "50_50") (pintype "passive+no_connect"))
    )
  )
)
